# firstTestUno.net
KiCad netlist of a schematic drawn in EAGLE
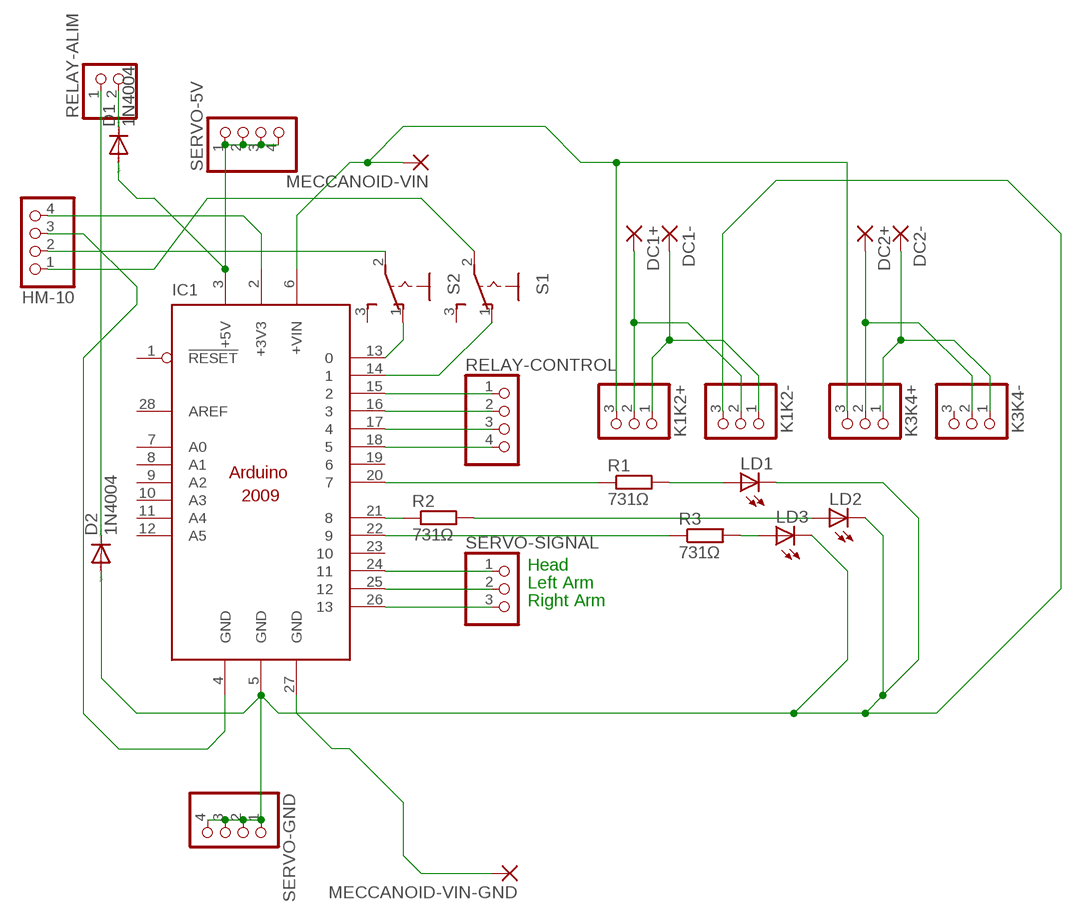
[diagram p0: schematic, sheet 1]

(export (version "E")
  (design (tool "Eeschema 10.0.6"))
  (components
    (comp (ref "D1")
      (value "1N4004")
      (footprint "eagle-import:DO41-10")
      (fields (field (name "MF") "MULTICOMP") (field (name "MPN") "1N4004+"))
      (libsource (lib "eagle-import") (part "1N4004"))
    )
    (comp (ref "D2")
      (value "1N4004")
      (footprint "eagle-import:DO41-10")
      (fields (field (name "MF") "MULTICOMP") (field (name "MPN") "1N4004+"))
      (libsource (lib "eagle-import") (part "1N4004"))
    )
    (comp (ref "DC1+")
      (value "1,6/0,8")
      (footprint "eagle-import:1,6_0,8")
      (fields (field (name "MF") "HELLERMANNTYTON") (field (name "MPN") "TK20-1,6/0,8-PVDF-CL"))
      (libsource (lib "eagle-import") (part "1,6/0,8"))
    )
    (comp (ref "DC1-")
      (value "1,6/0,8")
      (footprint "eagle-import:1,6_0,8")
      (fields (field (name "MF") "HELLERMANNTYTON") (field (name "MPN") "TK20-1,6/0,8-PVDF-CL"))
      (libsource (lib "eagle-import") (part "1,6/0,8"))
    )
    (comp (ref "DC2+")
      (value "1,6/0,8")
      (footprint "eagle-import:1,6_0,8")
      (fields (field (name "MF") "HELLERMANNTYTON") (field (name "MPN") "TK20-1,6/0,8-PVDF-CL"))
      (libsource (lib "eagle-import") (part "1,6/0,8"))
    )
    (comp (ref "DC2-")
      (value "1,6/0,8")
      (footprint "eagle-import:1,6_0,8")
      (fields (field (name "MF") "HELLERMANNTYTON") (field (name "MPN") "TK20-1,6/0,8-PVDF-CL"))
      (libsource (lib "eagle-import") (part "1,6/0,8"))
    )
    (comp (ref "HM-10")
      (value "PINHD-1X4")
      (footprint "eagle-import:1X04")
      (libsource (lib "eagle-import") (part "PINHD-1X4"))
    )
    (comp (ref "IC1")
      (value "ARDUINO2009_10")
      (footprint "eagle-import:ARDUINO2009")
      (libsource (lib "eagle-import") (part "ARDUINO2009_10"))
    )
    (comp (ref "K1K2+")
      (value "PINHD-1X3/90")
      (footprint "eagle-import:1X03_90")
      (libsource (lib "eagle-import") (part "PINHD-1X3/90"))
    )
    (comp (ref "K1K2-")
      (value "PINHD-1X3/90")
      (footprint "eagle-import:1X03_90")
      (libsource (lib "eagle-import") (part "PINHD-1X3/90"))
    )
    (comp (ref "K3K4+")
      (value "PINHD-1X3/90")
      (footprint "eagle-import:1X03_90")
      (libsource (lib "eagle-import") (part "PINHD-1X3/90"))
    )
    (comp (ref "K3K4-")
      (value "PINHD-1X3/90")
      (footprint "eagle-import:1X03_90")
      (libsource (lib "eagle-import") (part "PINHD-1X3/90"))
    )
    (comp (ref "LD1")
      (value "LED3MM")
      (footprint "eagle-import:LED3MM")
      (fields (field (name "MF") "MULTICOMP") (field (name "MPN") "LED 2F"))
      (libsource (lib "eagle-import") (part "LED3MM"))
    )
    (comp (ref "LD2")
      (value "LED3MM")
      (footprint "eagle-import:LED3MM")
      (fields (field (name "MF") "MULTICOMP") (field (name "MPN") "LED 2F"))
      (libsource (lib "eagle-import") (part "LED3MM"))
    )
    (comp (ref "LD3")
      (value "LED3MM")
      (footprint "eagle-import:LED3MM")
      (fields (field (name "MF") "MULTICOMP") (field (name "MPN") "LED 2F"))
      (libsource (lib "eagle-import") (part "LED3MM"))
    )
    (comp (ref "MECCANOID-VIN")
      (value "1,6/0,8")
      (footprint "eagle-import:1,6_0,8")
      (fields (field (name "MF") "HELLERMANNTYTON") (field (name "MPN") "TK20-1,6/0,8-PVDF-CL"))
      (libsource (lib "eagle-import") (part "1,6/0,8"))
    )
    (comp (ref "MECCANOID-VIN-GND")
      (value "1,6/0,8")
      (footprint "eagle-import:1,6_0,8")
      (fields (field (name "MF") "HELLERMANNTYTON") (field (name "MPN") "TK20-1,6/0,8-PVDF-CL"))
      (libsource (lib "eagle-import") (part "1,6/0,8"))
    )
    (comp (ref "R1")
      (value "731Ω")
      (footprint "eagle-import:0207_5V")
      (fields (field (name "MF") "WURTH ELEKTRONIK") (field (name "MPN") "74270035"))
      (libsource (lib "eagle-import") (part "R-EU_0207/5V"))
    )
    (comp (ref "R2")
      (value "731Ω")
      (footprint "eagle-import:0207_5V")
      (fields (field (name "MF") "WURTH ELEKTRONIK") (field (name "MPN") "74270035"))
      (libsource (lib "eagle-import") (part "R-EU_0207/5V"))
    )
    (comp (ref "R3")
      (value "731Ω")
      (footprint "eagle-import:0207_5V")
      (fields (field (name "MF") "WURTH ELEKTRONIK") (field (name "MPN") "74270035"))
      (libsource (lib "eagle-import") (part "R-EU_0207/5V"))
    )
    (comp (ref "RELAY-ALIM")
      (value "PINHD-1X2")
      (footprint "eagle-import:1X02")
      (fields (field (name "MF") "EPCOS") (field (name "MPN") "B65659F0001X023"))
      (libsource (lib "eagle-import") (part "PINHD-1X2"))
    )
    (comp (ref "RELAY-CONTROL")
      (value "PINHD-1X4")
      (footprint "eagle-import:1X04")
      (libsource (lib "eagle-import") (part "PINHD-1X4"))
    )
    (comp (ref "S1")
      (value "255SB")
      (footprint "eagle-import:255SB")
      (fields (field (name "MF") "ITT CANNON") (field (name "MPN") "CA3106E32-55SB03"))
      (libsource (lib "eagle-import") (part "255SB"))
    )
    (comp (ref "S2")
      (value "255SB")
      (footprint "eagle-import:255SB")
      (fields (field (name "MF") "ITT CANNON") (field (name "MPN") "CA3106E32-55SB03"))
      (libsource (lib "eagle-import") (part "255SB"))
    )
    (comp (ref "SERVO-5V")
      (value "PINHD-1X4")
      (footprint "eagle-import:1X04")
      (libsource (lib "eagle-import") (part "PINHD-1X4"))
    )
    (comp (ref "SERVO-GND")
      (value "PINHD-1X4")
      (footprint "eagle-import:1X04")
      (libsource (lib "eagle-import") (part "PINHD-1X4"))
    )
    (comp (ref "SERVO-SIGNAL")
      (value "PINHD-1X3")
      (footprint "eagle-import:1X03")
      (fields (field (name "MF") "TE CONNECTIVITY") (field (name "MPN") "V23234A0001X038-EV-144"))
      (libsource (lib "eagle-import") (part "PINHD-1X3"))
    )
  )
  (nets
    (net (code "1") (name "Net-(D1-PadC)") (class "Default")
      (node (ref "D1") (pin "C") (pinfunction "C_C") (pintype "passive"))
      (node (ref "RELAY-ALIM") (pin "2") (pinfunction "2_2") (pintype "passive"))
    )
    (net (code "2") (name "Net-(D2-PadC)") (class "Default")
      (node (ref "D2") (pin "C") (pinfunction "C_C") (pintype "passive"))
      (node (ref "RELAY-ALIM") (pin "1") (pinfunction "1_1") (pintype "passive"))
    )
    (net (code "3") (name "Net-(DC1+-P)") (class "Default")
      (node (ref "DC1+") (pin "1") (pinfunction "P_1") (pintype "passive"))
      (node (ref "K1K2+") (pin "2") (pinfunction "2_2") (pintype "passive"))
      (node (ref "K1K2-") (pin "2") (pinfunction "2_2") (pintype "passive"))
    )
    (net (code "4") (name "Net-(DC1--P)") (class "Default")
      (node (ref "DC1-") (pin "1") (pinfunction "P_1") (pintype "passive"))
      (node (ref "K1K2+") (pin "1") (pinfunction "1_1") (pintype "passive"))
      (node (ref "K1K2-") (pin "1") (pinfunction "1_1") (pintype "passive"))
    )
    (net (code "5") (name "Net-(DC2+-P)") (class "Default")
      (node (ref "DC2+") (pin "1") (pinfunction "P_1") (pintype "passive"))
      (node (ref "K3K4+") (pin "2") (pinfunction "2_2") (pintype "passive"))
      (node (ref "K3K4-") (pin "2") (pinfunction "2_2") (pintype "passive"))
    )
    (net (code "6") (name "Net-(DC2--P)") (class "Default")
      (node (ref "DC2-") (pin "1") (pinfunction "P_1") (pintype "passive"))
      (node (ref "K3K4+") (pin "1") (pinfunction "1_1") (pintype "passive"))
      (node (ref "K3K4-") (pin "1") (pinfunction "1_1") (pintype "passive"))
    )
    (net (code "7") (name "Net-(HM-10-Pad3)") (class "Default")
      (node (ref "HM-10") (pin "3") (pinfunction "3_3") (pintype "passive"))
      (node (ref "IC1") (pin "4") (pinfunction "GND_4") (pintype "power_in"))
    )
    (net (code "8") (name "Net-(IC1-+3V3)") (class "Default")
      (node (ref "HM-10") (pin "4") (pinfunction "4_4") (pintype "passive"))
      (node (ref "IC1") (pin "2") (pinfunction "+3V3_2") (pintype "power_in"))
    )
    (net (code "9") (name "Net-(IC1-+5V)") (class "Default")
      (node (ref "D1") (pin "A") (pinfunction "A_A") (pintype "passive"))
      (node (ref "IC1") (pin "3") (pinfunction "+5V_3") (pintype "power_in"))
      (node (ref "SERVO-5V") (pin "1") (pinfunction "1_1") (pintype "passive"))
      (node (ref "SERVO-5V") (pin "2") (pinfunction "2_2") (pintype "passive"))
      (node (ref "SERVO-5V") (pin "3") (pinfunction "3_3") (pintype "passive"))
      (node (ref "SERVO-5V") (pin "4") (pinfunction "4_4") (pintype "passive"))
    )
    (net (code "10") (name "Net-(IC1-+VIN)") (class "Default")
      (node (ref "IC1") (pin "6") (pinfunction "+VIN_6") (pintype "bidirectional"))
      (node (ref "K1K2+") (pin "3") (pinfunction "3_3") (pintype "passive"))
      (node (ref "K3K4+") (pin "3") (pinfunction "3_3") (pintype "passive"))
      (node (ref "MECCANOID-VIN") (pin "1") (pinfunction "P_1") (pintype "passive"))
    )
    (net (code "11") (name "Net-(IC1-0)") (class "Default")
      (node (ref "IC1") (pin "13") (pinfunction "0_13") (pintype "bidirectional"))
      (node (ref "S2") (pin "1") (pinfunction "O_1") (pintype "passive"))
    )
    (net (code "12") (name "Net-(IC1-1)") (class "Default")
      (node (ref "IC1") (pin "14") (pinfunction "1_14") (pintype "bidirectional"))
      (node (ref "S1") (pin "1") (pinfunction "O_1") (pintype "passive"))
    )
    (net (code "13") (name "Net-(IC1-2)") (class "Default")
      (node (ref "IC1") (pin "15") (pinfunction "2_15") (pintype "bidirectional"))
      (node (ref "RELAY-CONTROL") (pin "1") (pinfunction "1_1") (pintype "passive"))
    )
    (net (code "14") (name "Net-(IC1-3)") (class "Default")
      (node (ref "IC1") (pin "16") (pinfunction "3_16") (pintype "bidirectional"))
      (node (ref "RELAY-CONTROL") (pin "2") (pinfunction "2_2") (pintype "passive"))
    )
    (net (code "15") (name "Net-(IC1-4)") (class "Default")
      (node (ref "IC1") (pin "17") (pinfunction "4_17") (pintype "bidirectional"))
      (node (ref "RELAY-CONTROL") (pin "3") (pinfunction "3_3") (pintype "passive"))
    )
    (net (code "16") (name "Net-(IC1-5)") (class "Default")
      (node (ref "IC1") (pin "18") (pinfunction "5_18") (pintype "bidirectional"))
      (node (ref "RELAY-CONTROL") (pin "4") (pinfunction "4_4") (pintype "passive"))
    )
    (net (code "17") (name "Net-(IC1-7)") (class "Default")
      (node (ref "IC1") (pin "20") (pinfunction "7_20") (pintype "bidirectional"))
      (node (ref "R1") (pin "1") (pinfunction "1_1") (pintype "passive"))
    )
    (net (code "18") (name "Net-(IC1-8)") (class "Default")
      (node (ref "IC1") (pin "21") (pinfunction "8_21") (pintype "bidirectional"))
      (node (ref "R2") (pin "1") (pinfunction "1_1") (pintype "passive"))
    )
    (net (code "19") (name "Net-(IC1-9)") (class "Default")
      (node (ref "IC1") (pin "22") (pinfunction "9_22") (pintype "bidirectional"))
      (node (ref "R3") (pin "1") (pinfunction "1_1") (pintype "passive"))
    )
    (net (code "20") (name "Net-(IC1-11)") (class "Default")
      (node (ref "IC1") (pin "24") (pinfunction "11_24") (pintype "bidirectional"))
      (node (ref "SERVO-SIGNAL") (pin "1") (pinfunction "1_1") (pintype "passive"))
    )
    (net (code "21") (name "Net-(IC1-12)") (class "Default")
      (node (ref "IC1") (pin "25") (pinfunction "12_25") (pintype "bidirectional"))
      (node (ref "SERVO-SIGNAL") (pin "2") (pinfunction "2_2") (pintype "passive"))
    )
    (net (code "22") (name "Net-(IC1-13)") (class "Default")
      (node (ref "IC1") (pin "26") (pinfunction "13_26") (pintype "bidirectional"))
      (node (ref "SERVO-SIGNAL") (pin "3") (pinfunction "3_3") (pintype "passive"))
    )
    (net (code "23") (name "Net-(LD1-C)") (class "Default")
      (node (ref "D2") (pin "A") (pinfunction "A_A") (pintype "passive"))
      (node (ref "IC1") (pin "5") (pinfunction "GND_5") (pintype "power_in"))
      (node (ref "K1K2-") (pin "3") (pinfunction "3_3") (pintype "passive"))
      (node (ref "LD1") (pin "K") (pinfunction "C_K") (pintype "passive"))
      (node (ref "LD2") (pin "K") (pinfunction "C_K") (pintype "passive"))
      (node (ref "LD3") (pin "K") (pinfunction "C_K") (pintype "passive"))
      (node (ref "SERVO-GND") (pin "1") (pinfunction "1_1") (pintype "passive"))
      (node (ref "SERVO-GND") (pin "2") (pinfunction "2_2") (pintype "passive"))
      (node (ref "SERVO-GND") (pin "3") (pinfunction "3_3") (pintype "passive"))
      (node (ref "SERVO-GND") (pin "4") (pinfunction "4_4") (pintype "passive"))
    )
    (net (code "24") (name "Net-(LD1-PadA)") (class "Default")
      (node (ref "LD1") (pin "A") (pinfunction "A_A") (pintype "passive"))
      (node (ref "R1") (pin "2") (pinfunction "2_2") (pintype "passive"))
    )
    (net (code "25") (name "Net-(LD2-PadA)") (class "Default")
      (node (ref "LD2") (pin "A") (pinfunction "A_A") (pintype "passive"))
      (node (ref "R2") (pin "2") (pinfunction "2_2") (pintype "passive"))
    )
    (net (code "26") (name "Net-(LD3-PadA)") (class "Default")
      (node (ref "LD3") (pin "A") (pinfunction "A_A") (pintype "passive"))
      (node (ref "R3") (pin "2") (pinfunction "2_2") (pintype "passive"))
    )
    (net (code "27") (name "Net-(MECCANOID-VIN-GND-P)") (class "Default")
      (node (ref "IC1") (pin "27") (pinfunction "GND_27") (pintype "power_in"))
      (node (ref "MECCANOID-VIN-GND") (pin "1") (pinfunction "P_1") (pintype "passive"))
    )
    (net (code "28") (name "Net-(S1-P)") (class "Default")
      (node (ref "HM-10") (pin "1") (pinfunction "1_1") (pintype "passive"))
      (node (ref "S1") (pin "2") (pinfunction "P_2") (pintype "passive"))
    )
    (net (code "29") (name "Net-(S2-P)") (class "Default")
      (node (ref "HM-10") (pin "2") (pinfunction "2_2") (pintype "passive"))
      (node (ref "S2") (pin "2") (pinfunction "P_2") (pintype "passive"))
    )
    (net (code "30") (name "unconnected-(IC1-6-Pad19)") (class "Default")
      (node (ref "IC1") (pin "19") (pinfunction "6_19") (pintype "bidirectional"))
    )
    (net (code "31") (name "unconnected-(IC1-10-Pad23)") (class "Default")
      (node (ref "IC1") (pin "23") (pinfunction "10_23") (pintype "bidirectional"))
    )
    (net (code "32") (name "unconnected-(IC1-A0-Pad7)") (class "Default")
      (node (ref "IC1") (pin "7") (pinfunction "A0_7") (pintype "bidirectional"))
    )
    (net (code "33") (name "unconnected-(IC1-A1-Pad8)") (class "Default")
      (node (ref "IC1") (pin "8") (pinfunction "A1_8") (pintype "bidirectional"))
    )
    (net (code "34") (name "unconnected-(IC1-A2-Pad9)") (class "Default")
      (node (ref "IC1") (pin "9") (pinfunction "A2_9") (pintype "bidirectional"))
    )
    (net (code "35") (name "unconnected-(IC1-A3-Pad10)") (class "Default")
      (node (ref "IC1") (pin "10") (pinfunction "A3_10") (pintype "bidirectional"))
    )
    (net (code "36") (name "unconnected-(IC1-A4-Pad11)") (class "Default")
      (node (ref "IC1") (pin "11") (pinfunction "A4_11") (pintype "bidirectional"))
    )
    (net (code "37") (name "unconnected-(IC1-A5-Pad12)") (class "Default")
      (node (ref "IC1") (pin "12") (pinfunction "A5_12") (pintype "bidirectional"))
    )
    (net (code "38") (name "unconnected-(IC1-AREF-Pad28)") (class "Default")
      (node (ref "IC1") (pin "28") (pinfunction "AREF_28") (pintype "bidirectional"))
    )
    (net (code "39") (name "unconnected-(IC1-~{RESET}-Pad1)") (class "Default")
      (node (ref "IC1") (pin "1") (pinfunction "~{RESET}_1") (pintype "bidirectional"))
    )
    (net (code "40") (name "unconnected-(K3K4--Pad3)") (class "Default")
      (node (ref "K3K4-") (pin "3") (pinfunction "3_3") (pintype "passive"))
    )
    (net (code "41") (name "unconnected-(S1-S-Pad3)") (class "Default")
      (node (ref "S1") (pin "3") (pinfunction "S_3") (pintype "passive"))
    )
    (net (code "42") (name "unconnected-(S2-S-Pad3)") (class "Default")
      (node (ref "S2") (pin "3") (pinfunction "S_3") (pintype "passive"))
    )
  )
)
